# four_axis_part1.net
KiCad netlist of a schematic drawn in Altium Designer
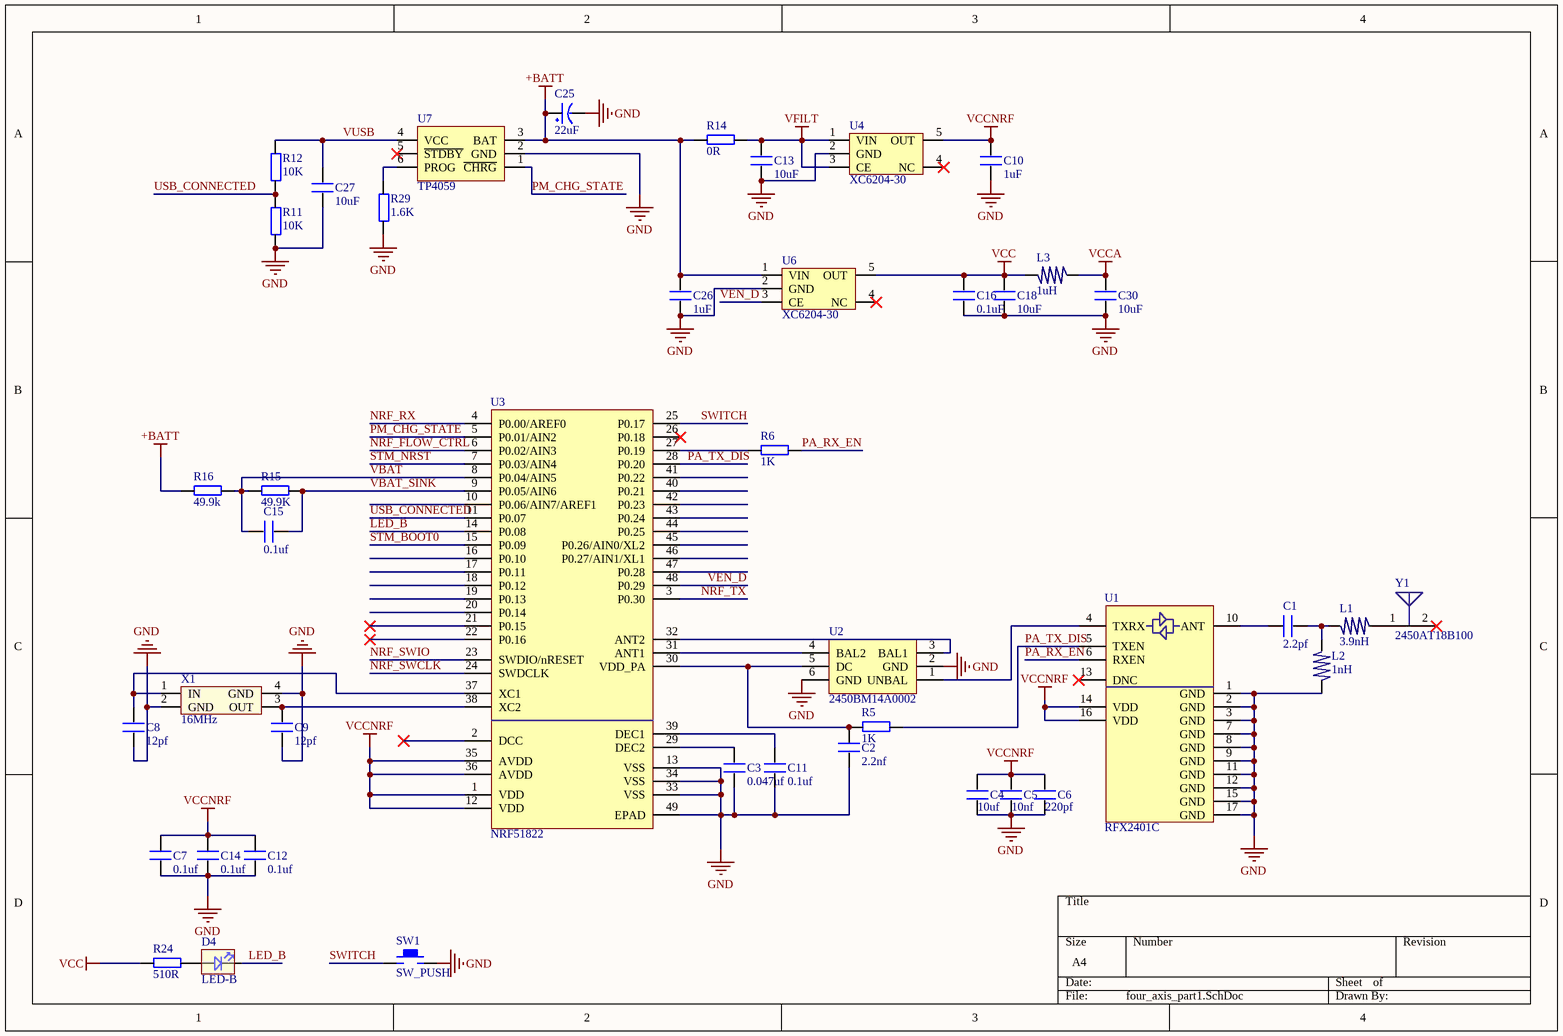
[diagram p0: four_axis_part1.SchDoc]

(export (version "E")
  (design (tool "Eeschema 10.0.6"))
  (components
    (comp (ref "C1") (value "2.2pf") (footprint "0603P") (libsource (lib "MiniFly ") (part "C")))
    (comp (ref "C2") (value "2.2nf") (footprint "0603P") (libsource (lib "MiniFly ") (part "C")))
    (comp (ref "C3") (value "0.047uf") (footprint "0603P") (libsource (lib "MiniFly ") (part "C")))
    (comp (ref "C4") (value "10uf") (footprint "0603P") (libsource (lib "MiniFly ") (part "C")))
    (comp (ref "C5") (value "10nf") (footprint "0603P") (libsource (lib "MiniFly ") (part "C")))
    (comp (ref "C6") (value "220pf") (footprint "0603P") (libsource (lib "MiniFly ") (part "C")))
    (comp (ref "C7") (value "0.1uf") (footprint "0603P") (libsource (lib "MiniFly ") (part "C")))
    (comp (ref "C8") (value "12pf") (footprint "0603P") (libsource (lib "MiniFly ") (part "C")))
    (comp (ref "C9") (value "12pf") (footprint "0603P") (libsource (lib "MiniFly ") (part "C")))
    (comp (ref "C10") (value "1uF") (footprint "0603P") (libsource (lib "MiniFly ") (part "C")))
    (comp (ref "C11") (value "0.1uf") (footprint "0603P") (libsource (lib "MiniFly ") (part "C")))
    (comp (ref "C12") (value "0.1uf") (footprint "0603P") (libsource (lib "MiniFly ") (part "C")))
    (comp (ref "C13") (value "10uF") (footprint "0603P") (libsource (lib "MiniFly ") (part "C")))
    (comp (ref "C14") (value "0.1uf") (footprint "0603P") (libsource (lib "MiniFly ") (part "C")))
    (comp (ref "C15") (value "0.1uf") (footprint "0603P") (libsource (lib "MiniFly ") (part "C")))
    (comp (ref "C16") (value "0.1uF") (footprint "0603P") (libsource (lib "MiniFly ") (part "C")))
    (comp (ref "C18") (value "10uF") (footprint "0603P") (libsource (lib "MiniFly ") (part "C")))
    (comp (ref "C25") (value "22uF") (footprint "C0805 钽电容") (libsource (lib "MiniFly ") (part "CAP")))
    (comp (ref "C26") (value "1uF") (footprint "0603P") (libsource (lib "MiniFly ") (part "C")))
    (comp (ref "C27") (value "10uF") (footprint "0603P") (libsource (lib "MiniFly ") (part "C")))
    (comp (ref "C30") (value "10uF") (footprint "0603P") (libsource (lib "MiniFly ") (part "C")))
    (comp (ref "D4")
      (value "LED-B")
      (footprint "LED1206  侧贴")
      (description "LED 1206 侧贴  单色")
      (libsource (lib "MiniFly ") (part "LED 1206 侧贴  单色"))
    )
    (comp (ref "L1") (value "3.9nH") (footprint "0603P") (libsource (lib "") (part "L_1")))
    (comp (ref "L2") (value "1nH") (footprint "0603P") (libsource (lib "") (part "L_2")))
    (comp (ref "L3") (value "1uH") (footprint "0603P") (libsource (lib "MiniFly ") (part "L")))
    (comp (ref "R5") (value "1K") (footprint "0402") (libsource (lib "MiniFly ") (part "R")))
    (comp (ref "R6") (value "1K") (footprint "0402") (libsource (lib "MiniFly ") (part "R")))
    (comp (ref "R11") (value "10K") (footprint "0402") (libsource (lib "MiniFly ") (part "R")))
    (comp (ref "R12") (value "10K") (footprint "0402") (libsource (lib "MiniFly ") (part "R")))
    (comp (ref "R14") (value "0R") (footprint "0402") (libsource (lib "MiniFly ") (part "R")))
    (comp (ref "R15") (value "49.9K") (footprint "0402") (libsource (lib "MiniFly ") (part "R")))
    (comp (ref "R16") (value "49.9k") (footprint "0402") (libsource (lib "MiniFly ") (part "R")))
    (comp (ref "R24") (value "510R") (footprint "0402") (libsource (lib "MiniFly ") (part "R")))
    (comp (ref "R29") (value "1.6K") (footprint "0402") (libsource (lib "MiniFly ") (part "R")))
    (comp (ref "SW1") (value "SW_PUSH") (footprint "KEY_2S") (libsource (lib "MiniFly ") (part "KEY")))
    (comp (ref "U1") (value "RFX2401C") (footprint "QFN16M") (libsource (lib "MiniFly ") (part "RFX2401C")))
    (comp (ref "U2") (value "2450BM14A0002") (footprint "0603-6") (libsource (lib "MiniFly ") (part "BALUN")))
    (comp (ref "U3")
      (value "NRF51822")
      (footprint "QFN48M-04")
      (libsource (lib "MiniFly ") (part "NRF51822"))
    )
    (comp (ref "U4") (value "XC6204-30") (footprint "SOT23-5S") (libsource (lib "MiniFly ") (part "XC6204")))
    (comp (ref "U6") (value "XC6204-30") (footprint "SOT23-5S") (libsource (lib "MiniFly ") (part "XC6204")))
    (comp (ref "U7") (value "TP4059") (footprint "SOT23-6S") (libsource (lib "MiniFly ") (part "TP4059")))
    (comp (ref "X1")
      (value "16MHz")
      (footprint "XTAL3225   无源")
      (description "无源贴片晶振")
      (libsource (lib "MiniFly ") (part "XTAL-无源贴片"))
    )
    (comp (ref "Y1")
      (value "2450AT18B100")
      (footprint "1206")
      (libsource (lib "MiniFly ") (part "CHIP_ANTENNA"))
    )
  )
  (nets
    (net (code "1") (name "+BATT") (class "Default")
      (node (ref "C25") (pin "1") (pinfunction "VCC_1") (pintype "passive"))
      (node (ref "C26") (pin "2") (pintype "passive"))
      (node (ref "R14") (pin "2") (pintype "passive"))
      (node (ref "R16") (pin "2") (pintype "passive"))
      (node (ref "U6") (pin "1") (pinfunction "VIN_1") (pintype "passive"))
      (node (ref "U7") (pin "3") (pinfunction "BAT_3") (pintype "passive"))
    )
    (net (code "2") (name "/LED_B") (class "Default")
      (node (ref "D4") (pin "1") (pinfunction "1_1") (pintype "passive"))
      (node (ref "U3") (pin "14") (pinfunction "P0.08_14") (pintype "passive"))
    )
    (net (code "3") (name "/NRF_FLOW_CTRL") (class "Default")
      (node (ref "U3") (pin "6") (pinfunction "P0.02/AIN3_6") (pintype "passive"))
    )
    (net (code "4") (name "/NRF_RX") (class "Default")
      (node (ref "U3") (pin "4") (pinfunction "P0.00/AREF0_4") (pintype "passive"))
    )
    (net (code "5") (name "/NRF_SWCLK") (class "Default")
      (node (ref "U3") (pin "24") (pinfunction "SWDCLK_24") (pintype "passive"))
    )
    (net (code "6") (name "/NRF_SWIO") (class "Default")
      (node (ref "U3") (pin "23") (pinfunction "SWDIO/nRESET_23") (pintype "passive"))
    )
    (net (code "7") (name "/NRF_TX") (class "Default")
      (node (ref "U3") (pin "3") (pinfunction "P0.30_3") (pintype "passive"))
    )
    (net (code "8") (name "/PA_RX_EN") (class "Default")
      (node (ref "R6") (pin "1") (pintype "passive"))
      (node (ref "U1") (pin "6") (pinfunction "RXEN_6") (pintype "passive"))
    )
    (net (code "9") (name "/PA_TX_DIS") (class "Default")
      (node (ref "R5") (pin "1") (pintype "passive"))
      (node (ref "U1") (pin "5") (pinfunction "TXEN_5") (pintype "passive"))
      (node (ref "U3") (pin "28") (pinfunction "P0.20_28") (pintype "passive"))
    )
    (net (code "10") (name "/PM_CHG_STATE") (class "Default")
      (node (ref "U3") (pin "5") (pinfunction "P0.01/AIN2_5") (pintype "passive"))
      (node (ref "U7") (pin "1") (pinfunction "~{CHRG}_1") (pintype "passive"))
    )
    (net (code "11") (name "/STM_BOOT0") (class "Default")
      (node (ref "U3") (pin "15") (pinfunction "P0.09_15") (pintype "passive"))
    )
    (net (code "12") (name "/STM_NRST") (class "Default")
      (node (ref "U3") (pin "7") (pinfunction "P0.03/AIN4_7") (pintype "passive"))
    )
    (net (code "13") (name "/SWITCH") (class "Default")
      (node (ref "SW1") (pin "1") (pinfunction "1_1") (pintype "passive"))
      (node (ref "U3") (pin "25") (pinfunction "P0.17_25") (pintype "passive"))
    )
    (net (code "14") (name "/USB_CONNECTED") (class "Default")
      (node (ref "R11") (pin "2") (pintype "passive"))
      (node (ref "R12") (pin "1") (pintype "passive"))
      (node (ref "U3") (pin "11") (pinfunction "P0.07_11") (pintype "passive"))
    )
    (net (code "15") (name "/VBAT") (class "Default")
      (node (ref "C15") (pin "2") (pintype "passive"))
      (node (ref "R15") (pin "2") (pintype "passive"))
      (node (ref "R16") (pin "1") (pintype "passive"))
      (node (ref "U3") (pin "8") (pinfunction "P0.04/AIN5_8") (pintype "passive"))
    )
    (net (code "16") (name "/VBAT_SINK") (class "Default")
      (node (ref "C15") (pin "1") (pintype "passive"))
      (node (ref "R15") (pin "1") (pintype "passive"))
      (node (ref "U3") (pin "9") (pinfunction "P0.05/AIN6_9") (pintype "passive"))
    )
    (net (code "17") (name "/VEN_D") (class "Default")
      (node (ref "U3") (pin "48") (pinfunction "P0.29_48") (pintype "passive"))
      (node (ref "U6") (pin "3") (pinfunction "CE_3") (pintype "passive"))
    )
    (net (code "18") (name "/VUSB") (class "Default")
      (node (ref "C27") (pin "2") (pintype "passive"))
      (node (ref "R12") (pin "2") (pintype "passive"))
      (node (ref "U7") (pin "4") (pinfunction "VCC_4") (pintype "passive"))
    )
    (net (code "19") (name "GND") (class "Default")
      (node (ref "C10") (pin "1") (pintype "passive"))
      (node (ref "C11") (pin "2") (pintype "passive"))
      (node (ref "C12") (pin "2") (pintype "passive"))
      (node (ref "C13") (pin "1") (pintype "passive"))
      (node (ref "C14") (pin "2") (pintype "passive"))
      (node (ref "C16") (pin "1") (pintype "passive"))
      (node (ref "C18") (pin "1") (pintype "passive"))
      (node (ref "C2") (pin "1") (pintype "passive"))
      (node (ref "C25") (pin "2") (pinfunction "GND_2") (pintype "passive"))
      (node (ref "C26") (pin "1") (pintype "passive"))
      (node (ref "C27") (pin "1") (pintype "passive"))
      (node (ref "C3") (pin "2") (pintype "passive"))
      (node (ref "C30") (pin "1") (pintype "passive"))
      (node (ref "C4") (pin "1") (pintype "passive"))
      (node (ref "C5") (pin "1") (pintype "passive"))
      (node (ref "C6") (pin "1") (pintype "passive"))
      (node (ref "C7") (pin "2") (pintype "passive"))
      (node (ref "C8") (pin "2") (pintype "passive"))
      (node (ref "C9") (pin "2") (pintype "passive"))
      (node (ref "L2") (pin "2") (pintype "passive"))
      (node (ref "R11") (pin "1") (pintype "passive"))
      (node (ref "R29") (pin "1") (pintype "passive"))
      (node (ref "SW1") (pin "2") (pinfunction "2_2") (pintype "passive"))
      (node (ref "U1") (pin "1") (pinfunction "GND_1") (pintype "passive"))
      (node (ref "U1") (pin "11") (pinfunction "GND_11") (pintype "passive"))
      (node (ref "U1") (pin "12") (pinfunction "GND_12") (pintype "passive"))
      (node (ref "U1") (pin "15") (pinfunction "GND_15") (pintype "passive"))
      (node (ref "U1") (pin "17") (pinfunction "GND_17") (pintype "passive"))
      (node (ref "U1") (pin "2") (pinfunction "GND_2") (pintype "passive"))
      (node (ref "U1") (pin "3") (pinfunction "GND_3") (pintype "passive"))
      (node (ref "U1") (pin "7") (pinfunction "GND_7") (pintype "passive"))
      (node (ref "U1") (pin "8") (pinfunction "GND_8") (pintype "passive"))
      (node (ref "U1") (pin "9") (pinfunction "GND_9") (pintype "passive"))
      (node (ref "U2") (pin "2") (pinfunction "GND_2") (pintype "passive"))
      (node (ref "U2") (pin "6") (pinfunction "GND_6") (pintype "passive"))
      (node (ref "U3") (pin "13") (pinfunction "VSS_13") (pintype "passive"))
      (node (ref "U3") (pin "33") (pinfunction "VSS_33") (pintype "passive"))
      (node (ref "U3") (pin "34") (pinfunction "VSS_34") (pintype "passive"))
      (node (ref "U3") (pin "49") (pinfunction "EPAD_49") (pintype "passive"))
      (node (ref "U4") (pin "2") (pinfunction "GND_2") (pintype "passive"))
      (node (ref "U6") (pin "2") (pinfunction "GND_2") (pintype "passive"))
      (node (ref "U7") (pin "2") (pinfunction "GND_2") (pintype "passive"))
      (node (ref "X1") (pin "2") (pinfunction "GND_2") (pintype "passive"))
      (node (ref "X1") (pin "4") (pinfunction "GND_4") (pintype "passive"))
    )
    (net (code "20") (name "Net-(C1-Pad1)") (class "Default")
      (node (ref "C1") (pin "1") (pintype "passive"))
      (node (ref "L1") (pin "1") (pintype "passive"))
      (node (ref "L2") (pin "1") (pintype "passive"))
    )
    (net (code "21") (name "Net-(D4-Pad3)") (class "Default")
      (node (ref "D4") (pin "3") (pinfunction "3_3") (pintype "passive"))
      (node (ref "R24") (pin "1") (pintype "passive"))
    )
    (net (code "22") (name "Net-(U1-ANT)") (class "Default")
      (node (ref "C1") (pin "2") (pintype "passive"))
      (node (ref "U1") (pin "10") (pinfunction "ANT_10") (pintype "passive"))
    )
    (net (code "23") (name "Net-(U1-TXRX)") (class "Default")
      (node (ref "U1") (pin "4") (pinfunction "TXRX_4") (pintype "passive"))
      (node (ref "U2") (pin "1") (pinfunction "UNBAL_1") (pintype "passive"))
    )
    (net (code "24") (name "Net-(U2-BAL1)") (class "Default")
      (node (ref "U2") (pin "3") (pinfunction "BAL1_3") (pintype "passive"))
      (node (ref "U3") (pin "32") (pinfunction "ANT2_32") (pintype "passive"))
    )
    (net (code "25") (name "Net-(U2-BAL2)") (class "Default")
      (node (ref "U2") (pin "4") (pinfunction "BAL2_4") (pintype "passive"))
      (node (ref "U3") (pin "31") (pinfunction "ANT1_31") (pintype "passive"))
    )
    (net (code "26") (name "Net-(U2-DC)") (class "Default")
      (node (ref "C2") (pin "2") (pintype "passive"))
      (node (ref "R5") (pin "2") (pintype "passive"))
      (node (ref "U2") (pin "5") (pinfunction "DC_5") (pintype "passive"))
      (node (ref "U3") (pin "30") (pinfunction "VDD_PA_30") (pintype "passive"))
    )
    (net (code "27") (name "Net-(U3-DEC1)") (class "Default")
      (node (ref "C11") (pin "1") (pintype "passive"))
      (node (ref "U3") (pin "39") (pinfunction "DEC1_39") (pintype "passive"))
    )
    (net (code "28") (name "Net-(U3-DEC2)") (class "Default")
      (node (ref "C3") (pin "1") (pintype "passive"))
      (node (ref "U3") (pin "29") (pinfunction "DEC2_29") (pintype "passive"))
    )
    (net (code "29") (name "Net-(U3-P0.19)") (class "Default")
      (node (ref "R6") (pin "2") (pintype "passive"))
      (node (ref "U3") (pin "27") (pinfunction "P0.19_27") (pintype "passive"))
    )
    (net (code "30") (name "Net-(U3-XC1)") (class "Default")
      (node (ref "C8") (pin "1") (pintype "passive"))
      (node (ref "U3") (pin "37") (pinfunction "XC1_37") (pintype "passive"))
      (node (ref "X1") (pin "1") (pinfunction "IN_1") (pintype "passive"))
    )
    (net (code "31") (name "Net-(U3-XC2)") (class "Default")
      (node (ref "C9") (pin "1") (pintype "passive"))
      (node (ref "U3") (pin "38") (pinfunction "XC2_38") (pintype "passive"))
      (node (ref "X1") (pin "3") (pinfunction "OUT_3") (pintype "passive"))
    )
    (net (code "32") (name "Net-(U7-PROG)") (class "Default")
      (node (ref "R29") (pin "2") (pintype "passive"))
      (node (ref "U7") (pin "6") (pinfunction "PROG_6") (pintype "passive"))
    )
    (net (code "33") (name "Net-(Y1-FP)") (class "Default")
      (node (ref "L1") (pin "2") (pintype "passive"))
      (node (ref "Y1") (pin "1") (pinfunction "FP_1") (pintype "passive"))
    )
    (net (code "34") (name "VCC") (class "Default")
      (node (ref "C16") (pin "2") (pintype "passive"))
      (node (ref "C18") (pin "2") (pintype "passive"))
      (node (ref "L3") (pin "2") (pintype "passive"))
      (node (ref "R24") (pin "2") (pintype "passive"))
      (node (ref "U6") (pin "5") (pinfunction "OUT_5") (pintype "passive"))
    )
    (net (code "35") (name "VCCA") (class "Default")
      (node (ref "C30") (pin "2") (pintype "passive"))
      (node (ref "L3") (pin "1") (pintype "passive"))
    )
    (net (code "36") (name "VCCNRF") (class "Default")
      (node (ref "C10") (pin "2") (pintype "passive"))
      (node (ref "C12") (pin "1") (pintype "passive"))
      (node (ref "C14") (pin "1") (pintype "passive"))
      (node (ref "C4") (pin "2") (pintype "passive"))
      (node (ref "C5") (pin "2") (pintype "passive"))
      (node (ref "C6") (pin "2") (pintype "passive"))
      (node (ref "C7") (pin "1") (pintype "passive"))
      (node (ref "U1") (pin "14") (pinfunction "VDD_14") (pintype "passive"))
      (node (ref "U1") (pin "16") (pinfunction "VDD_16") (pintype "passive"))
      (node (ref "U3") (pin "1") (pinfunction "VDD_1") (pintype "passive"))
      (node (ref "U3") (pin "12") (pinfunction "VDD_12") (pintype "passive"))
      (node (ref "U3") (pin "35") (pinfunction "AVDD_35") (pintype "passive"))
      (node (ref "U3") (pin "36") (pinfunction "AVDD_36") (pintype "passive"))
      (node (ref "U4") (pin "5") (pinfunction "OUT_5") (pintype "passive"))
    )
    (net (code "37") (name "VFILT") (class "Default")
      (node (ref "C13") (pin "2") (pintype "passive"))
      (node (ref "R14") (pin "1") (pintype "passive"))
      (node (ref "U4") (pin "1") (pinfunction "VIN_1") (pintype "passive"))
      (node (ref "U4") (pin "3") (pinfunction "CE_3") (pintype "passive"))
    )
    (net (code "38") (name "unconnected-(D4-Pad2)") (class "Default")
      (node (ref "D4") (pin "2") (pinfunction "2_2") (pintype "passive"))
    )
    (net (code "39") (name "unconnected-(U1-DNC-Pad13)") (class "Default")
      (node (ref "U1") (pin "13") (pinfunction "DNC_13") (pintype "passive+no_connect"))
    )
    (net (code "40") (name "unconnected-(U3-DCC-Pad2)") (class "Default")
      (node (ref "U3") (pin "2") (pinfunction "DCC_2") (pintype "passive+no_connect"))
    )
    (net (code "41") (name "unconnected-(U3-P0.06{slash}AIN7{slash}AREF1-Pad10)") (class "Default")
      (node (ref "U3") (pin "10") (pinfunction "P0.06/AIN7/AREF1_10") (pintype "passive"))
    )
    (net (code "42") (name "unconnected-(U3-P0.10-Pad16)") (class "Default")
      (node (ref "U3") (pin "16") (pinfunction "P0.10_16") (pintype "passive"))
    )
    (net (code "43") (name "unconnected-(U3-P0.11-Pad17)") (class "Default")
      (node (ref "U3") (pin "17") (pinfunction "P0.11_17") (pintype "passive"))
    )
    (net (code "44") (name "unconnected-(U3-P0.12-Pad18)") (class "Default")
      (node (ref "U3") (pin "18") (pinfunction "P0.12_18") (pintype "passive"))
    )
    (net (code "45") (name "unconnected-(U3-P0.13-Pad19)") (class "Default")
      (node (ref "U3") (pin "19") (pinfunction "P0.13_19") (pintype "passive"))
    )
    (net (code "46") (name "unconnected-(U3-P0.14-Pad20)") (class "Default")
      (node (ref "U3") (pin "20") (pinfunction "P0.14_20") (pintype "passive"))
    )
    (net (code "47") (name "unconnected-(U3-P0.15-Pad21)") (class "Default")
      (node (ref "U3") (pin "21") (pinfunction "P0.15_21") (pintype "passive+no_connect"))
    )
    (net (code "48") (name "unconnected-(U3-P0.16-Pad22)") (class "Default")
      (node (ref "U3") (pin "22") (pinfunction "P0.16_22") (pintype "passive+no_connect"))
    )
    (net (code "49") (name "unconnected-(U3-P0.18-Pad26)") (class "Default")
      (node (ref "U3") (pin "26") (pinfunction "P0.18_26") (pintype "passive+no_connect"))
    )
    (net (code "50") (name "unconnected-(U3-P0.21-Pad40)") (class "Default")
      (node (ref "U3") (pin "40") (pinfunction "P0.21_40") (pintype "passive"))
    )
    (net (code "51") (name "unconnected-(U3-P0.22-Pad41)") (class "Default")
      (node (ref "U3") (pin "41") (pinfunction "P0.22_41") (pintype "passive"))
    )
    (net (code "52") (name "unconnected-(U3-P0.23-Pad42)") (class "Default")
      (node (ref "U3") (pin "42") (pinfunction "P0.23_42") (pintype "passive"))
    )
    (net (code "53") (name "unconnected-(U3-P0.24-Pad43)") (class "Default")
      (node (ref "U3") (pin "43") (pinfunction "P0.24_43") (pintype "passive"))
    )
    (net (code "54") (name "unconnected-(U3-P0.25-Pad44)") (class "Default")
      (node (ref "U3") (pin "44") (pinfunction "P0.25_44") (pintype "passive"))
    )
    (net (code "55") (name "unconnected-(U3-P0.26{slash}AIN0{slash}XL2-Pad45)") (class "Default")
      (node (ref "U3") (pin "45") (pinfunction "P0.26/AIN0/XL2_45") (pintype "passive"))
    )
    (net (code "56") (name "unconnected-(U3-P0.27{slash}AIN1{slash}XL1-Pad46)") (class "Default")
      (node (ref "U3") (pin "46") (pinfunction "P0.27/AIN1/XL1_46") (pintype "passive"))
    )
    (net (code "57") (name "unconnected-(U3-P0.28-Pad47)") (class "Default")
      (node (ref "U3") (pin "47") (pinfunction "P0.28_47") (pintype "passive"))
    )
    (net (code "58") (name "unconnected-(U4-NC-Pad4)") (class "Default")
      (node (ref "U4") (pin "4") (pinfunction "NC_4") (pintype "passive+no_connect"))
    )
    (net (code "59") (name "unconnected-(U6-NC-Pad4)") (class "Default")
      (node (ref "U6") (pin "4") (pinfunction "NC_4") (pintype "passive+no_connect"))
    )
    (net (code "60") (name "unconnected-(U7-~{STDBY}-Pad5)") (class "Default")
      (node (ref "U7") (pin "5") (pinfunction "~{STDBY}_5") (pintype "passive+no_connect"))
    )
    (net (code "61") (name "unconnected-(Y1-NC-Pad2)") (class "Default")
      (node (ref "Y1") (pin "2") (pinfunction "NC_2") (pintype "passive+no_connect"))
    )
  )
)
